# wifi_tx.net
KiCad netlist of a schematic drawn in EasyEDA Pro
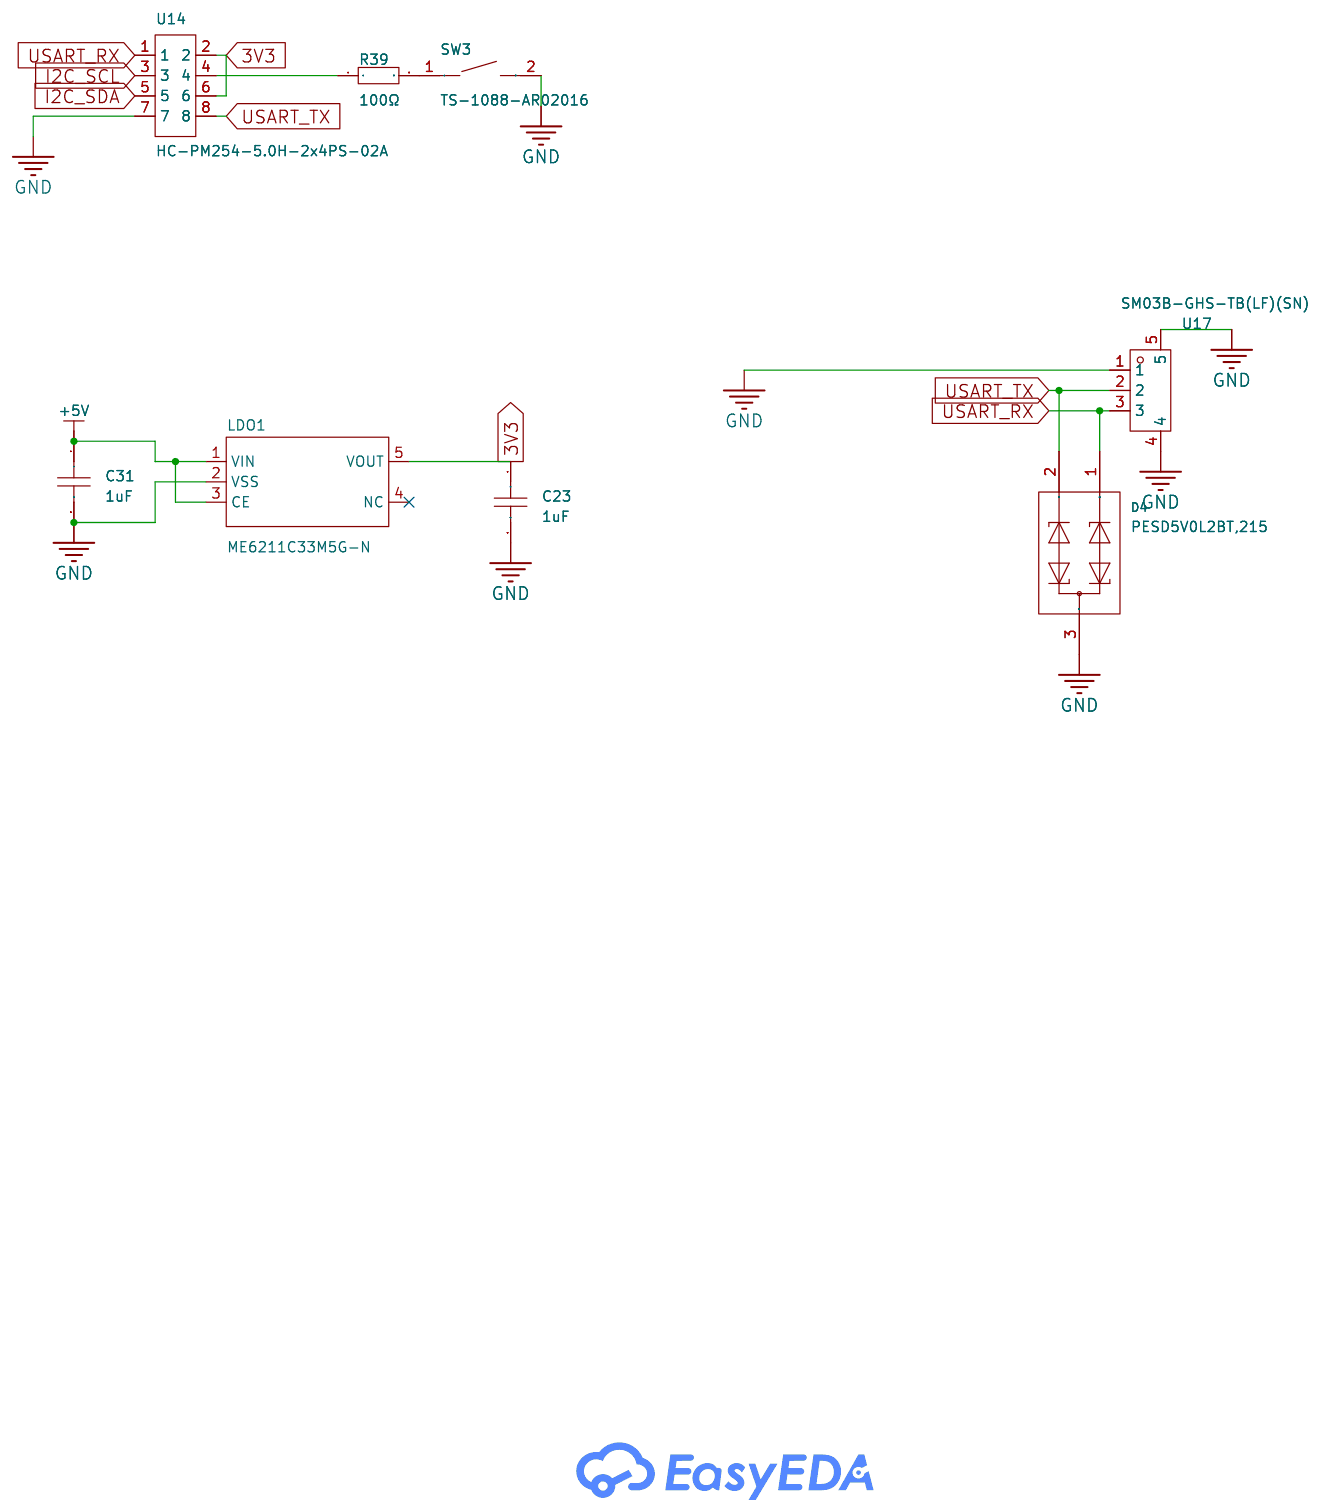
[diagram p0: schematic sheet]

(export (version "E")
  (design (tool "Eeschema 10.0.6"))
  (components
    (comp (ref "C23")
      (value "1uF")
      (footprint "easyedapro:C0603")
      (fields
        (field (name "Manufacturer Part") "CC0603KRX7R9BB105")
        (field (name "Manufacturer") "YAGEO(国巨)")
      )
      (libsource (lib "easyedapro") (part "CC0603KRX7R9BB105"))
    )
    (comp (ref "C31")
      (value "1uF")
      (footprint "easyedapro:C0603")
      (fields
        (field (name "Manufacturer Part") "CC0603KRX7R9BB105")
        (field (name "Manufacturer") "YAGEO(国巨)")
      )
      (libsource (lib "easyedapro") (part "CC0603KRX7R9BB105"))
    )
    (comp (ref "D4")
      (value "PESD5V0L2BT,215")
      (footprint "easyedapro:SOT-23-3_L2.9-W1.3-P1.90-LS2.4-BR")
      (description "Maximum Clamping Voltage:28V Breakdown Voltage:7V Number of Lines:双路 Type:ESD")
      (fields (field (name "Manufacturer") "Nexperia(安世)"))
      (libsource (lib "easyedapro") (part "PESD5V0L2BT,215"))
    )
    (comp (ref "LDO1")
      (value "ME6211C33M5G-N")
      (footprint "easyedapro:SOT-23-5_L3.0-W1.7-P0.95-LS2.8-BL")
      (fields (field (name "Manufacturer") "MICRONE(南京微盟)"))
      (libsource (lib "easyedapro") (part "ME6211C33M5G-N"))
    )
    (comp (ref "R39")
      (value "100Ω")
      (footprint "easyedapro:R0603")
      (fields (field (name "Manufacturer Part") "RC0603FR-07100RL") (field (name "Manufacturer") "YAGEO(国巨)"))
      (libsource (lib "easyedapro") (part "RC0603FR-07100RL"))
    )
    (comp (ref "SW3")
      (value "TS-1088-AR02016")
      (footprint "easyedapro:SW-SMD_L3.9-W3.0-P4.45")
      (fields (field (name "Manufacturer") "XUNPU(讯普)"))
      (libsource (lib "easyedapro") (part "TS-1088-AR02016"))
    )
    (comp (ref "U14")
      (value "HC-PM254-5.0H-2x4PS-02A")
      (footprint "easyedapro:HDR-SMD_8P-P2.54-V-F-R2-C4-S7.2-2")
      (fields (field (name "Manufacturer") "HC(虹成电子)"))
      (libsource (lib "easyedapro") (part "HC-PM254-5.0H-2X4PS-02A"))
    )
    (comp (ref "U17")
      (value "SM03B-GHS-TB(LF)(SN)")
      (footprint "easyedapro:CONN-TH_SM03B-GHS-TB-LF-SN")
      (fields (field (name "Manufacturer") "JST"))
      (libsource (lib "easyedapro") (part "SM03B-GHS-TB(LF)(SN)"))
    )
  )
  (nets
    (net (code "1") (name "+5V") (class "Default")
      (node (ref "C31") (pin "1") (pinfunction "1_1") (pintype "unspecified"))
      (node (ref "LDO1") (pin "1") (pinfunction "VIN_1") (pintype "unspecified"))
      (node (ref "LDO1") (pin "3") (pinfunction "CE_3") (pintype "unspecified"))
    )
    (net (code "2") (name "3V3") (class "Default")
      (node (ref "C23") (pin "1") (pinfunction "1_1") (pintype "unspecified"))
      (node (ref "LDO1") (pin "5") (pinfunction "VOUT_5") (pintype "unspecified"))
      (node (ref "U14") (pin "2") (pinfunction "2_2") (pintype "unspecified"))
      (node (ref "U14") (pin "6") (pinfunction "6_6") (pintype "unspecified"))
    )
    (net (code "3") (name "GND") (class "Default")
      (node (ref "C23") (pin "2") (pinfunction "2_2") (pintype "unspecified"))
      (node (ref "C31") (pin "2") (pinfunction "2_2") (pintype "unspecified"))
      (node (ref "D4") (pin "3") (pinfunction "DC_3") (pintype "input"))
      (node (ref "LDO1") (pin "2") (pinfunction "VSS_2") (pintype "unspecified"))
      (node (ref "SW3") (pin "2") (pinfunction "2_2") (pintype "unspecified"))
      (node (ref "U14") (pin "7") (pinfunction "7_7") (pintype "unspecified"))
      (node (ref "U17") (pin "1") (pinfunction "1_1") (pintype "unspecified"))
      (node (ref "U17") (pin "4") (pinfunction "4_4") (pintype "unspecified"))
      (node (ref "U17") (pin "5") (pinfunction "5_5") (pintype "unspecified"))
    )
    (net (code "4") (name "I2C_SCL") (class "Default")
      (node (ref "U14") (pin "3") (pinfunction "3_3") (pintype "unspecified"))
    )
    (net (code "5") (name "I2C_SDA") (class "Default")
      (node (ref "U14") (pin "5") (pinfunction "5_5") (pintype "unspecified"))
    )
    (net (code "6") (name "Net-(R39-Pad1)") (class "Default")
      (node (ref "R39") (pin "1") (pinfunction "1_1") (pintype "input"))
      (node (ref "U14") (pin "4") (pinfunction "4_4") (pintype "unspecified"))
    )
    (net (code "7") (name "Net-(R39-Pad2)") (class "Default")
      (node (ref "R39") (pin "2") (pinfunction "2_2") (pintype "input"))
      (node (ref "SW3") (pin "1") (pinfunction "1_1") (pintype "unspecified"))
    )
    (net (code "8") (name "USART_RX") (class "Default")
      (node (ref "D4") (pin "1") (pinfunction "C1_1") (pintype "input"))
      (node (ref "U14") (pin "1") (pinfunction "1_1") (pintype "unspecified"))
      (node (ref "U17") (pin "3") (pinfunction "3_3") (pintype "unspecified"))
    )
    (net (code "9") (name "USART_TX") (class "Default")
      (node (ref "D4") (pin "2") (pinfunction "C2_2") (pintype "input"))
      (node (ref "U14") (pin "8") (pinfunction "8_8") (pintype "unspecified"))
      (node (ref "U17") (pin "2") (pinfunction "2_2") (pintype "unspecified"))
    )
    (net (code "10") (name "unconnected-(LDO1-NC-Pad4)") (class "Default")
      (node (ref "LDO1") (pin "4") (pinfunction "NC_4") (pintype "unspecified+no_connect"))
    )
  )
)
